# BATTERY_SOC.net
KiCad netlist of a schematic drawn in Altium Designer
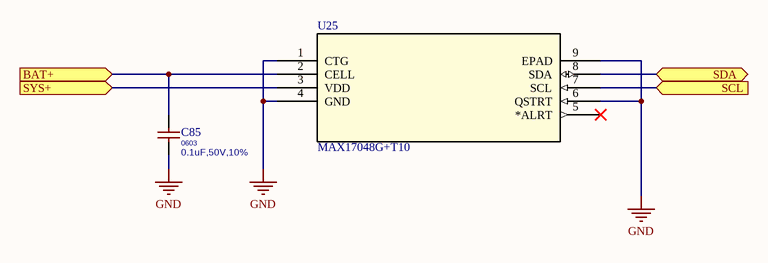
[diagram p0: BATTERY SOC.SchDoc]

(export (version "E")
  (design (tool "Eeschema 10.0.6"))
  (components
    (comp (ref "C85")
      (value "0.1uF,50V,10%")
      (footprint "C0603")
      (description "CAP CER 0.1UF 50V X7R 0603")
      (fields
        (field (name "MANUFACTURER") "Murata Electronics")
        (field (name "MPN") "GCM188R71H104KA57J")
        (field (name "PACKAGE") "0603")
      )
      (libsource (lib "RCL") (part "GCM188R71H104KA57J"))
    )
    (comp (ref "U25")
      (value "MAX17048G+T10")
      (footprint "21-0168E_T822-3_MXM")
      (description "No Description Available")
      (libsource (lib "IC") (part "MAX17048G+T10"))
    )
  )
  (nets
    (net (code "1") (name "/BAT+") (class "Default")
      (node (ref "C85") (pin "2") (pinfunction "2_2") (pintype "passive"))
      (node (ref "U25") (pin "2") (pinfunction "CELL_2") (pintype "passive"))
    )
    (net (code "2") (name "/SCL") (class "Default")
      (node (ref "U25") (pin "7") (pinfunction "SCL_7") (pintype "input"))
    )
    (net (code "3") (name "/SDA") (class "Default")
      (node (ref "U25") (pin "8") (pinfunction "SDA_8") (pintype "bidirectional"))
    )
    (net (code "4") (name "/SYS+") (class "Default")
      (node (ref "U25") (pin "3") (pinfunction "VDD_3") (pintype "power_in"))
    )
    (net (code "5") (name "GND") (class "Default")
      (node (ref "C85") (pin "1") (pinfunction "1_1") (pintype "passive"))
      (node (ref "U25") (pin "1") (pinfunction "CTG_1") (pintype "passive"))
      (node (ref "U25") (pin "4") (pinfunction "GND_4") (pintype "power_in"))
      (node (ref "U25") (pin "6") (pinfunction "QSTRT_6") (pintype "input"))
      (node (ref "U25") (pin "9") (pinfunction "EPAD_9") (pintype "passive"))
    )
    (net (code "6") (name "unconnected-(U25-*ALRT-Pad5)") (class "Default")
      (node (ref "U25") (pin "5") (pinfunction "*ALRT_5") (pintype "output+no_connect"))
    )
  )
)
